# FlowController.net
KiCad netlist of a schematic drawn in EAGLE
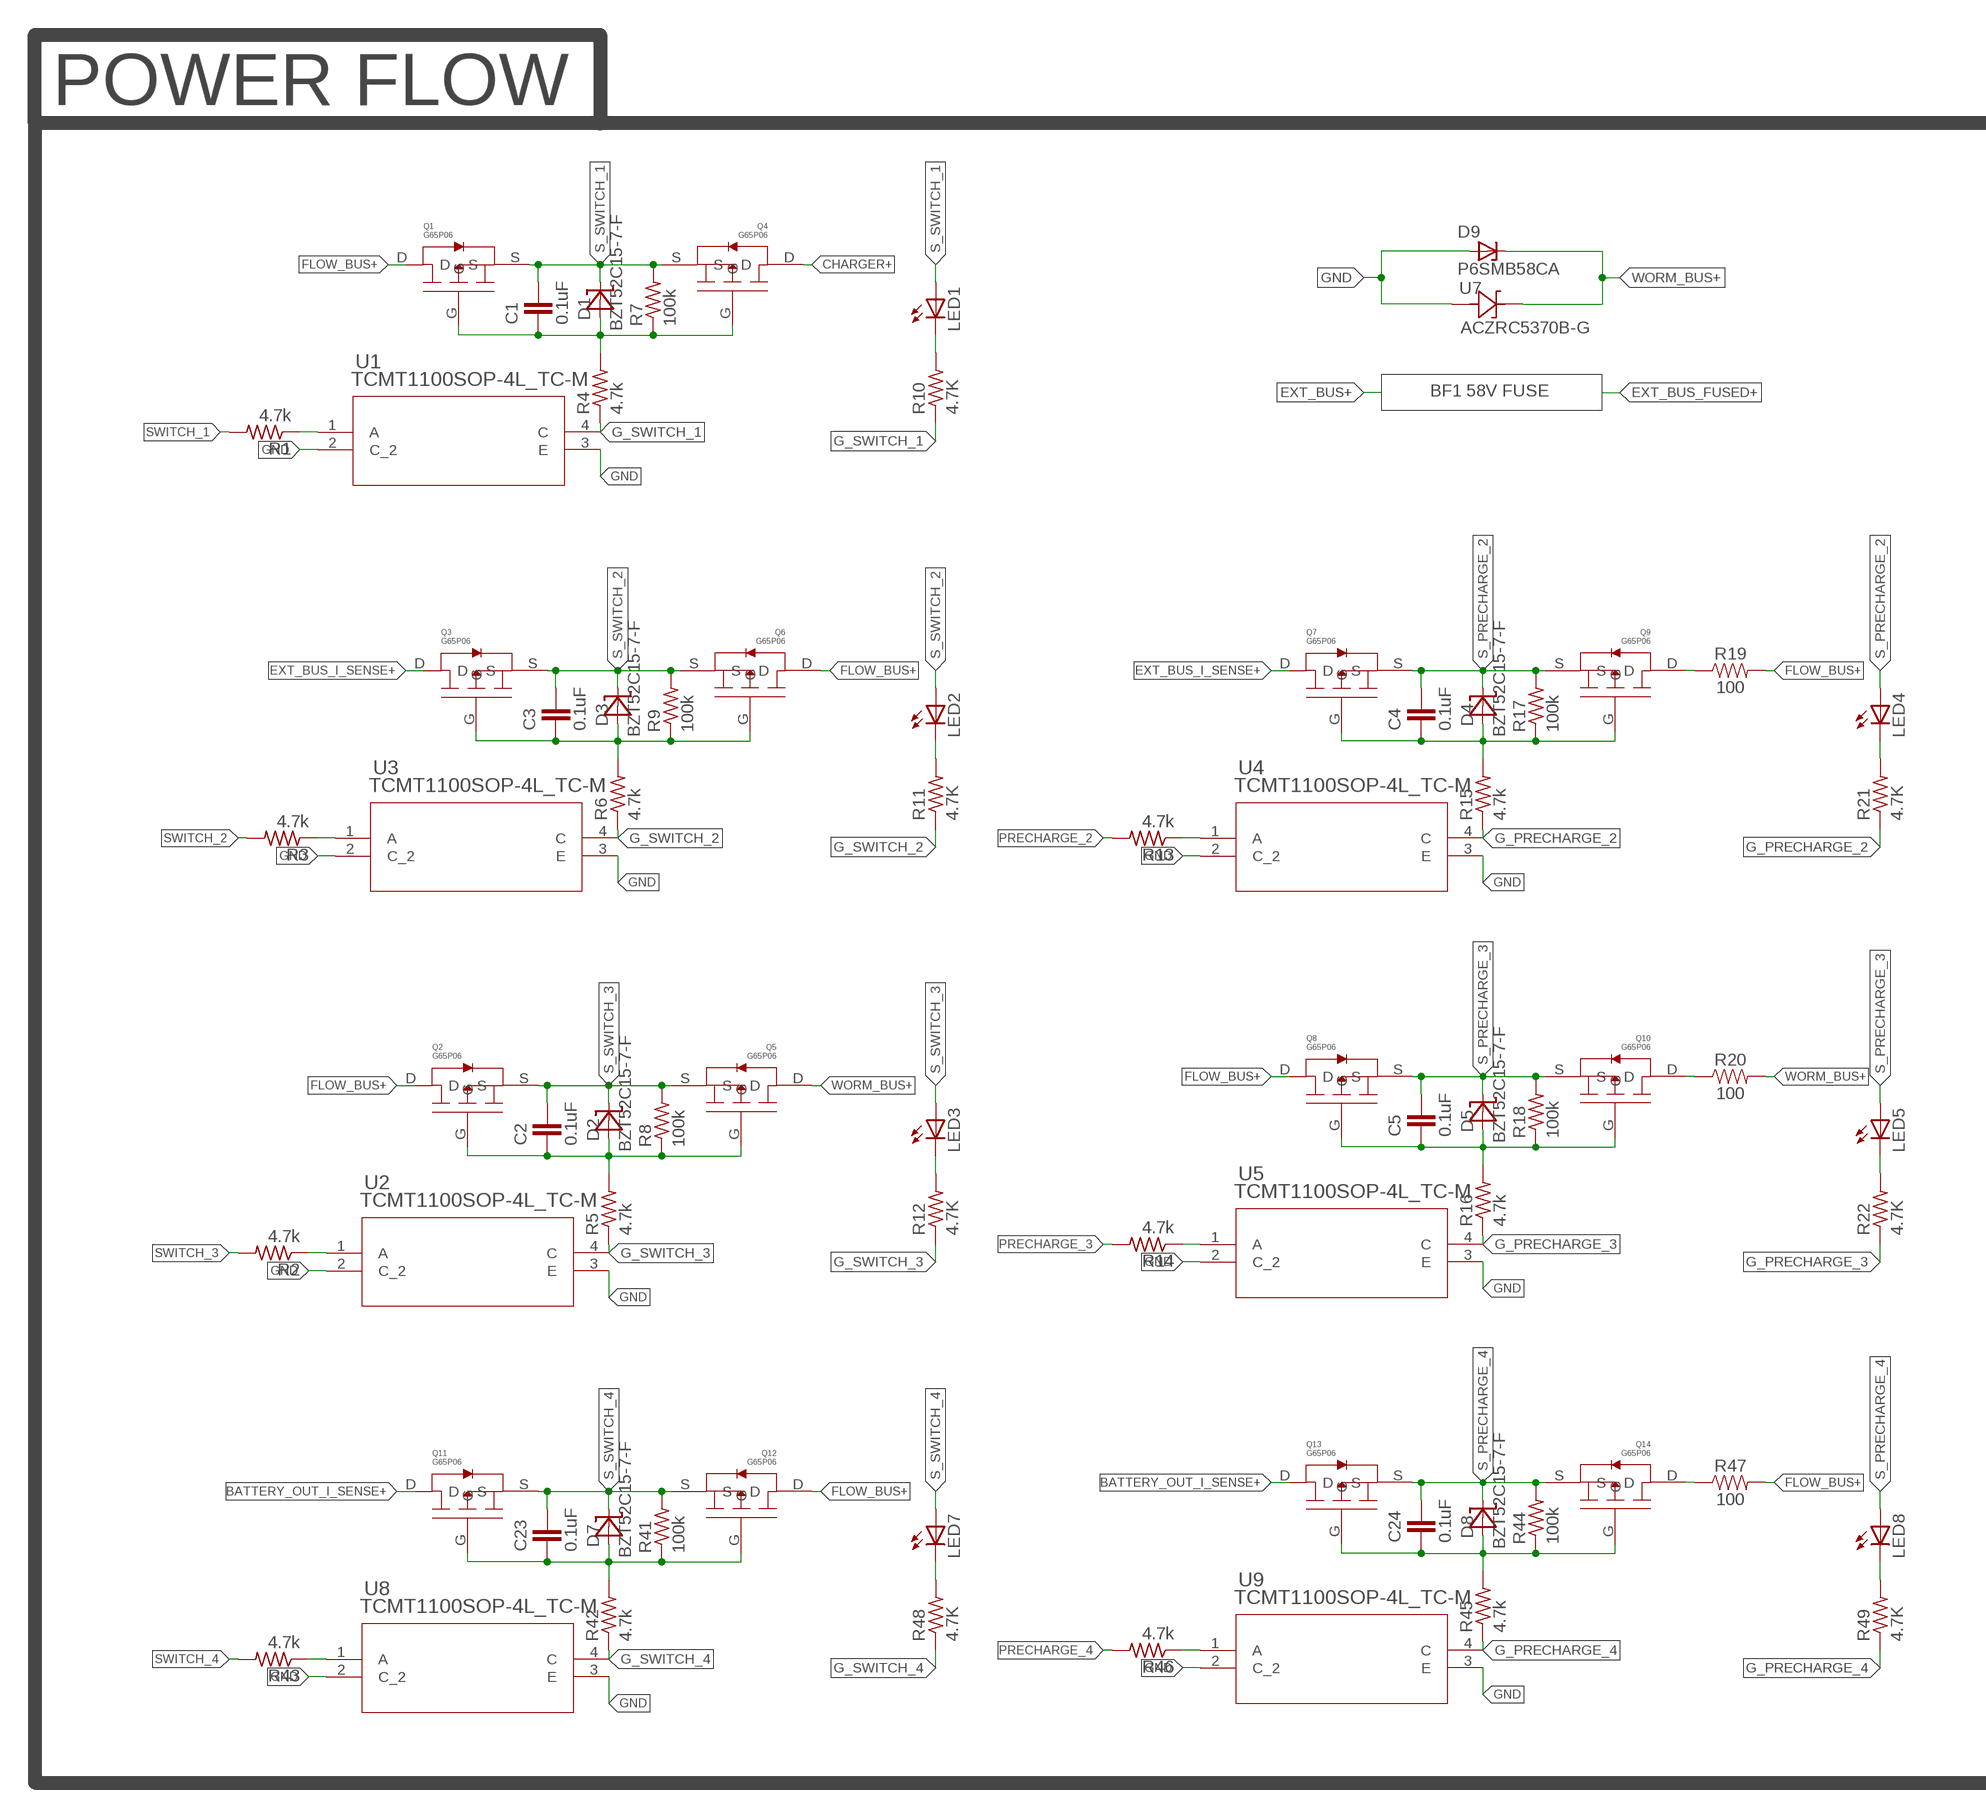
[diagram p0: schematic, sheet 1, part 1 of 2]
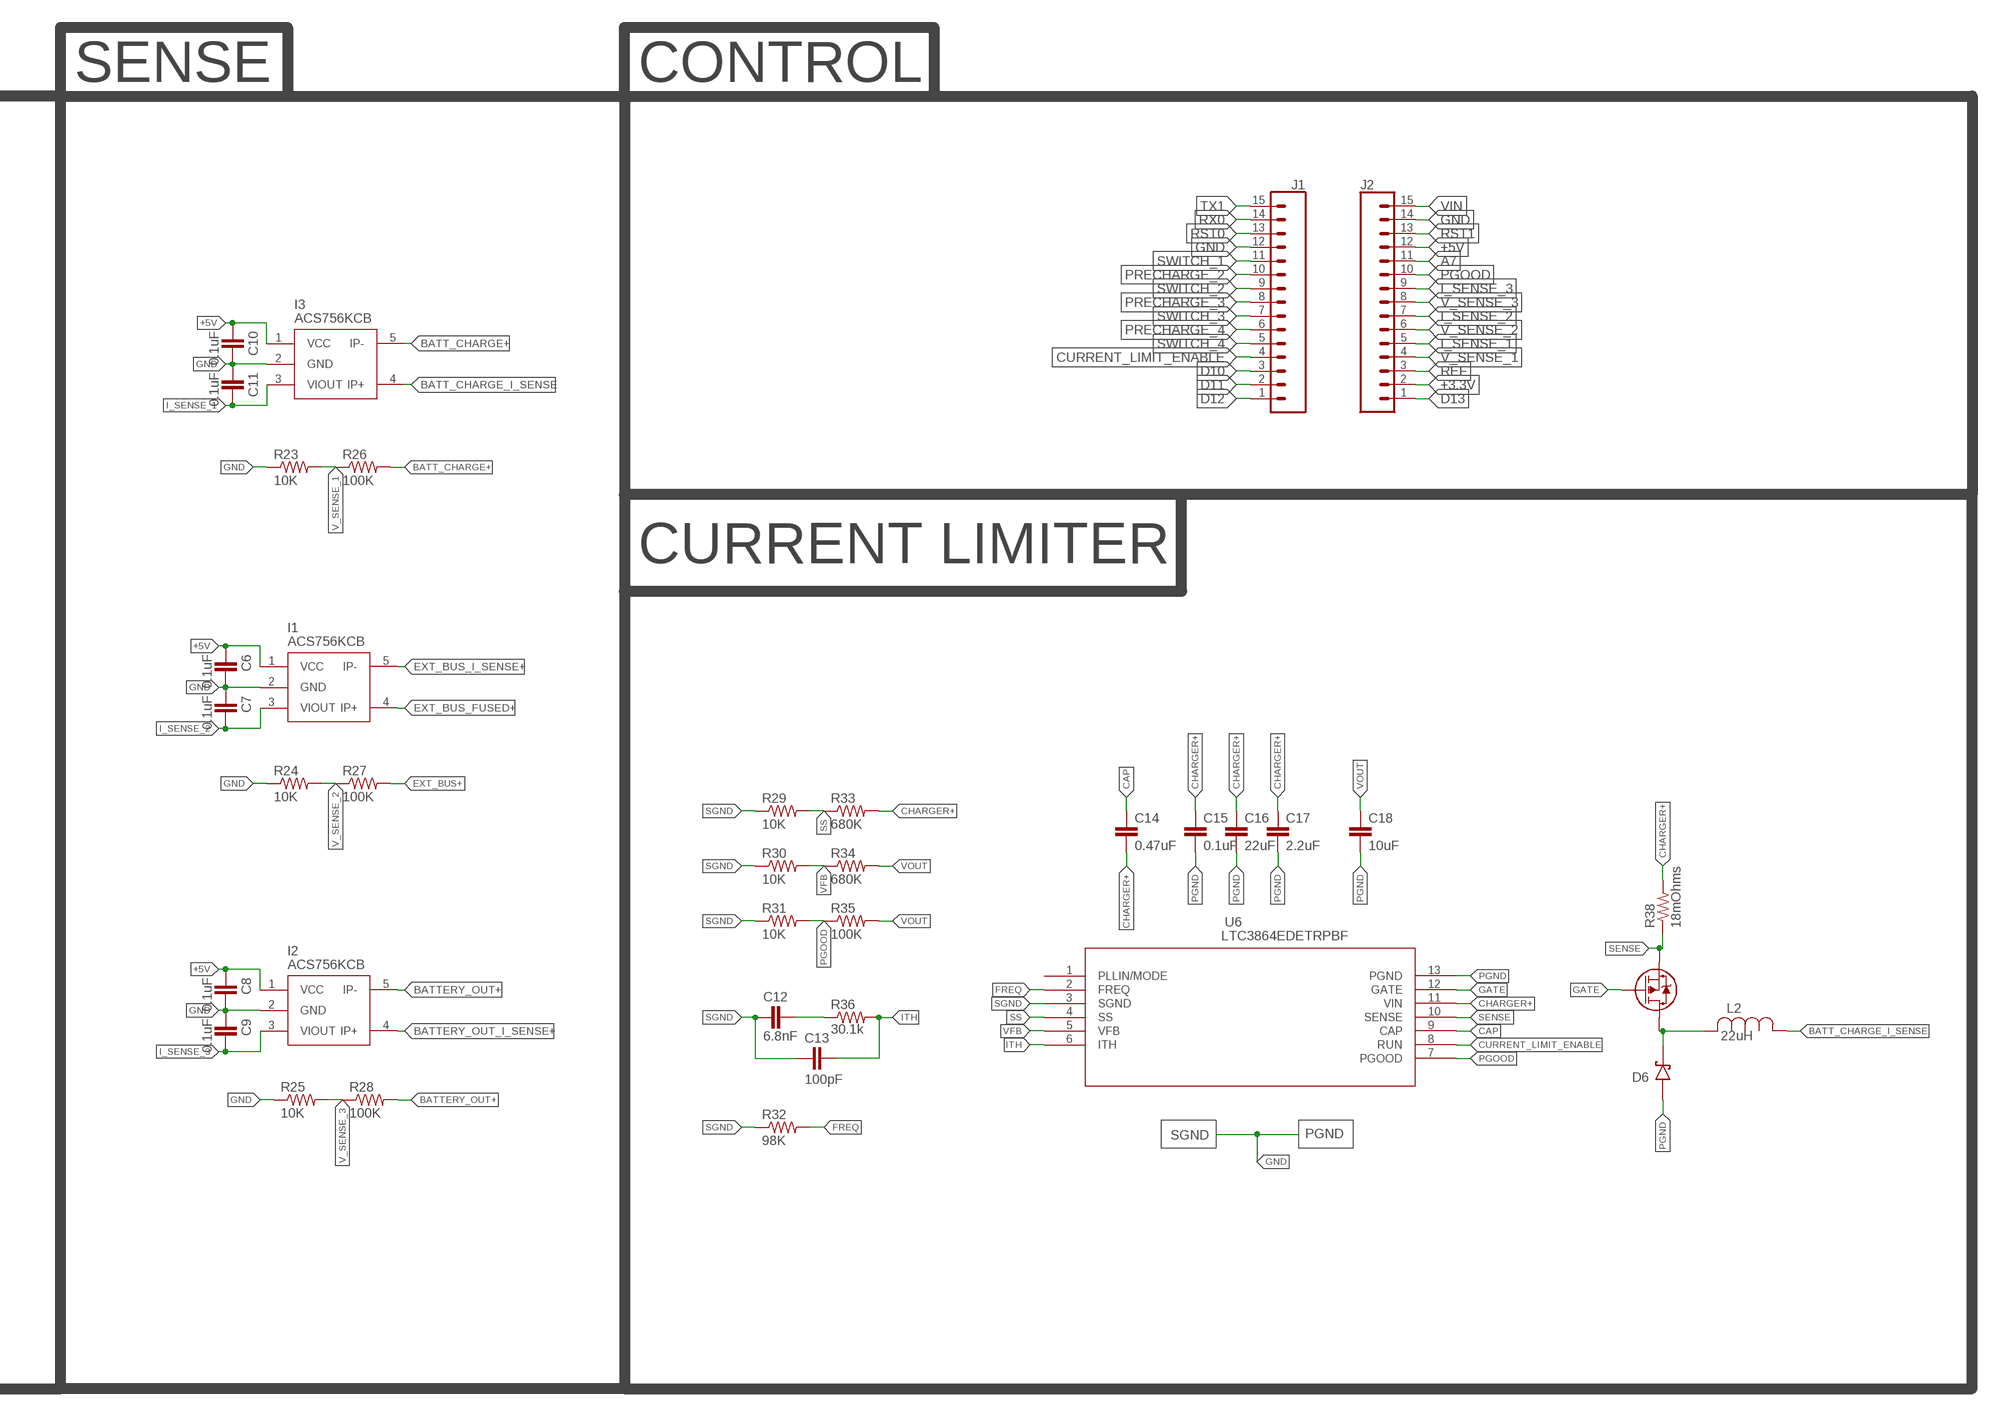
[diagram p1: schematic, sheet 1, part 2 of 2]

(export (version "E")
  (design (tool "Eeschema 10.0.6"))
  (components
    (comp (ref "C1")
      (value "0.1uF")
      (footprint "eagle-import:0805")
      (libsource (lib "eagle-import") (part "2.2UF-0805-25V-(+80/-20%)"))
    )
    (comp (ref "C2")
      (value "0.1uF")
      (footprint "eagle-import:0805")
      (libsource (lib "eagle-import") (part "2.2UF-0805-25V-(+80/-20%)"))
    )
    (comp (ref "C3")
      (value "0.1uF")
      (footprint "eagle-import:0805")
      (libsource (lib "eagle-import") (part "2.2UF-0805-25V-(+80/-20%)"))
    )
    (comp (ref "C4")
      (value "0.1uF")
      (footprint "eagle-import:0805")
      (libsource (lib "eagle-import") (part "2.2UF-0805-25V-(+80/-20%)"))
    )
    (comp (ref "C5")
      (value "0.1uF")
      (footprint "eagle-import:0805")
      (libsource (lib "eagle-import") (part "2.2UF-0805-25V-(+80/-20%)"))
    )
    (comp (ref "C6")
      (value "0.1uF")
      (footprint "eagle-import:0805")
      (libsource (lib "eagle-import") (part "2.2UF-0805-25V-(+80/-20%)"))
    )
    (comp (ref "C7")
      (value "0.1uF")
      (footprint "eagle-import:0805")
      (libsource (lib "eagle-import") (part "2.2UF-0805-25V-(+80/-20%)"))
    )
    (comp (ref "C8")
      (value "0.1uF")
      (footprint "eagle-import:0805")
      (libsource (lib "eagle-import") (part "2.2UF-0805-25V-(+80/-20%)"))
    )
    (comp (ref "C9")
      (value "0.1uF")
      (footprint "eagle-import:0805")
      (libsource (lib "eagle-import") (part "2.2UF-0805-25V-(+80/-20%)"))
    )
    (comp (ref "C10")
      (value "0.1uF")
      (footprint "eagle-import:0805")
      (libsource (lib "eagle-import") (part "2.2UF-0805-25V-(+80/-20%)"))
    )
    (comp (ref "C11")
      (value "0.1uF")
      (footprint "eagle-import:0805")
      (libsource (lib "eagle-import") (part "2.2UF-0805-25V-(+80/-20%)"))
    )
    (comp (ref "C12")
      (value "6.8nF")
      (footprint "eagle-import:0805")
      (libsource (lib "eagle-import") (part "2.2UF-0805-25V-(+80/-20%)"))
    )
    (comp (ref "C13")
      (value "100pF")
      (footprint "eagle-import:0805")
      (libsource (lib "eagle-import") (part "2.2UF-0805-25V-(+80/-20%)"))
    )
    (comp (ref "C14")
      (value "0.47uF")
      (footprint "eagle-import:0805")
      (libsource (lib "eagle-import") (part "2.2UF-0805-25V-(+80/-20%)"))
    )
    (comp (ref "C15")
      (value "0.1uF")
      (footprint "eagle-import:0805")
      (libsource (lib "eagle-import") (part "2.2UF-0805-25V-(+80/-20%)"))
    )
    (comp (ref "C16")
      (value "22uF")
      (footprint "eagle-import:1210")
      (libsource (lib "eagle-import") (part "10UF-1210-50V-20%"))
    )
    (comp (ref "C17")
      (value "2.2uF")
      (footprint "eagle-import:1210")
      (libsource (lib "eagle-import") (part "10UF-1210-50V-20%"))
    )
    (comp (ref "C18")
      (value "10uF")
      (footprint "eagle-import:1210")
      (libsource (lib "eagle-import") (part "10UF-1210-50V-20%"))
    )
    (comp (ref "C23")
      (value "0.1uF")
      (footprint "eagle-import:0805")
      (libsource (lib "eagle-import") (part "2.2UF-0805-25V-(+80/-20%)"))
    )
    (comp (ref "C24")
      (value "0.1uF")
      (footprint "eagle-import:0805")
      (libsource (lib "eagle-import") (part "2.2UF-0805-25V-(+80/-20%)"))
    )
    (comp (ref "D1")
      (value "BZT52C15-7-F")
      (footprint "eagle-import:SOD123")
      (fields (field (name "DIGI-KEY_PART_NUMBER") "BZT52C15-FDITR-ND") (field (name "MF") "Diodes Inc."))
      (libsource (lib "eagle-import") (part "BZT52C15-7-F"))
    )
    (comp (ref "D2")
      (value "BZT52C15-7-F")
      (footprint "eagle-import:SOD123")
      (fields (field (name "DIGI-KEY_PART_NUMBER") "BZT52C15-FDITR-ND") (field (name "MF") "Diodes Inc."))
      (libsource (lib "eagle-import") (part "BZT52C15-7-F"))
    )
    (comp (ref "D3")
      (value "BZT52C15-7-F")
      (footprint "eagle-import:SOD123")
      (fields (field (name "DIGI-KEY_PART_NUMBER") "BZT52C15-FDITR-ND") (field (name "MF") "Diodes Inc."))
      (libsource (lib "eagle-import") (part "BZT52C15-7-F"))
    )
    (comp (ref "D4")
      (value "BZT52C15-7-F")
      (footprint "eagle-import:SOD123")
      (fields (field (name "DIGI-KEY_PART_NUMBER") "BZT52C15-FDITR-ND") (field (name "MF") "Diodes Inc."))
      (libsource (lib "eagle-import") (part "BZT52C15-7-F"))
    )
    (comp (ref "D5")
      (value "BZT52C15-7-F")
      (footprint "eagle-import:SOD123")
      (fields (field (name "DIGI-KEY_PART_NUMBER") "BZT52C15-FDITR-ND") (field (name "MF") "Diodes Inc."))
      (libsource (lib "eagle-import") (part "BZT52C15-7-F"))
    )
    (comp (ref "D6")
      (value "MBR1560STR")
      (footprint "eagle-import:DIO_MBR1560STR")
      (fields (field (name "MF") "SMC Diode Solutions"))
      (libsource (lib "eagle-import") (part "MBR1560STR"))
    )
    (comp (ref "D7")
      (value "BZT52C15-7-F")
      (footprint "eagle-import:SOD123")
      (fields (field (name "DIGI-KEY_PART_NUMBER") "BZT52C15-FDITR-ND") (field (name "MF") "Diodes Inc."))
      (libsource (lib "eagle-import") (part "BZT52C15-7-F"))
    )
    (comp (ref "D8")
      (value "BZT52C15-7-F")
      (footprint "eagle-import:SOD123")
      (fields (field (name "DIGI-KEY_PART_NUMBER") "BZT52C15-FDITR-ND") (field (name "MF") "Diodes Inc."))
      (libsource (lib "eagle-import") (part "BZT52C15-7-F"))
    )
    (comp (ref "D9")
      (value "P6SMB58CA")
      (footprint "eagle-import:DO214AA")
      (fields (field (name "MF") "ON Semiconductor") (field (name "MPN") "1SMB5913BT3G"))
      (libsource (lib "eagle-import") (part "1SMB59BT3G13"))
    )
    (comp (ref "I1")
      (value "ACS756KCB")
      (footprint "eagle-import:ACS756KCB")
      (libsource (lib "eagle-import") (part "ACS756KCB"))
    )
    (comp (ref "I2")
      (value "ACS756KCB")
      (footprint "eagle-import:ACS756KCB")
      (libsource (lib "eagle-import") (part "ACS756KCB"))
    )
    (comp (ref "I3")
      (value "ACS756KCB")
      (footprint "eagle-import:ACS756KCB")
      (libsource (lib "eagle-import") (part "ACS756KCB"))
    )
    (comp (ref "J1")
      (value "CONN_15")
      (footprint "eagle-import:1X15")
      (libsource (lib "eagle-import") (part "CONN_15"))
    )
    (comp (ref "J2")
      (value "CONN_15")
      (footprint "eagle-import:1X15")
      (fields (field (name "SPICEPREFIX") "X"))
      (libsource (lib "eagle-import") (part "CONN_15"))
    )
    (comp (ref "L2")
      (value "22uH")
      (footprint "eagle-import:IND_IHLP-4040DZ_VIS")
      (fields
        (field (name "MANUFACTURER_PART_NUMBER") "IHLP4040DZER6R8M01")
        (field (name "COPYRIGHT") "Copyright (C) 2022 Ultra Librarian. All rights reserved.")
      )
      (libsource (lib "eagle-import") (part "IHLP4040DZER6R8M01"))
    )
    (comp (ref "LED1")
      (value "LEDCHIPLED_0805")
      (footprint "eagle-import:CHIPLED_0805")
      (libsource (lib "eagle-import") (part "LEDCHIPLED_0805"))
    )
    (comp (ref "LED2")
      (value "LEDCHIPLED_0805")
      (footprint "eagle-import:CHIPLED_0805")
      (libsource (lib "eagle-import") (part "LEDCHIPLED_0805"))
    )
    (comp (ref "LED3")
      (value "LEDCHIPLED_0805")
      (footprint "eagle-import:CHIPLED_0805")
      (libsource (lib "eagle-import") (part "LEDCHIPLED_0805"))
    )
    (comp (ref "LED4")
      (value "LEDCHIPLED_0805")
      (footprint "eagle-import:CHIPLED_0805")
      (libsource (lib "eagle-import") (part "LEDCHIPLED_0805"))
    )
    (comp (ref "LED5")
      (value "LEDCHIPLED_0805")
      (footprint "eagle-import:CHIPLED_0805")
      (libsource (lib "eagle-import") (part "LEDCHIPLED_0805"))
    )
    (comp (ref "LED7")
      (value "LEDCHIPLED_0805")
      (footprint "eagle-import:CHIPLED_0805")
      (libsource (lib "eagle-import") (part "LEDCHIPLED_0805"))
    )
    (comp (ref "LED8")
      (value "LEDCHIPLED_0805")
      (footprint "eagle-import:CHIPLED_0805")
      (libsource (lib "eagle-import") (part "LEDCHIPLED_0805"))
    )
    (comp (ref "Q1")
      (value "G65P06")
      (footprint "eagle-import:G65P06")
      (libsource (lib "eagle-import") (part "G65P06"))
    )
    (comp (ref "Q2")
      (value "G65P06")
      (footprint "eagle-import:G65P06")
      (libsource (lib "eagle-import") (part "G65P06"))
    )
    (comp (ref "Q3")
      (value "G65P06")
      (footprint "eagle-import:G65P06")
      (libsource (lib "eagle-import") (part "G65P06"))
    )
    (comp (ref "Q4")
      (value "G65P06")
      (footprint "eagle-import:G65P06")
      (libsource (lib "eagle-import") (part "G65P06"))
    )
    (comp (ref "Q5")
      (value "G65P06")
      (footprint "eagle-import:G65P06")
      (libsource (lib "eagle-import") (part "G65P06"))
    )
    (comp (ref "Q6")
      (value "G65P06")
      (footprint "eagle-import:G65P06")
      (libsource (lib "eagle-import") (part "G65P06"))
    )
    (comp (ref "Q7")
      (value "G65P06")
      (footprint "eagle-import:G65P06")
      (libsource (lib "eagle-import") (part "G65P06"))
    )
    (comp (ref "Q8")
      (value "G65P06")
      (footprint "eagle-import:G65P06")
      (libsource (lib "eagle-import") (part "G65P06"))
    )
    (comp (ref "Q9")
      (value "G65P06")
      (footprint "eagle-import:G65P06")
      (libsource (lib "eagle-import") (part "G65P06"))
    )
    (comp (ref "Q10")
      (value "G65P06")
      (footprint "eagle-import:G65P06")
      (libsource (lib "eagle-import") (part "G65P06"))
    )
    (comp (ref "Q11")
      (value "G65P06")
      (footprint "eagle-import:G65P06")
      (libsource (lib "eagle-import") (part "G65P06"))
    )
    (comp (ref "Q12")
      (value "G65P06")
      (footprint "eagle-import:G65P06")
      (libsource (lib "eagle-import") (part "G65P06"))
    )
    (comp (ref "Q13")
      (value "G65P06")
      (footprint "eagle-import:G65P06")
      (libsource (lib "eagle-import") (part "G65P06"))
    )
    (comp (ref "Q14")
      (value "G65P06")
      (footprint "eagle-import:G65P06")
      (libsource (lib "eagle-import") (part "G65P06"))
    )
    (comp (ref "R1")
      (value "4.7k")
      (footprint "eagle-import:M0805")
      (libsource (lib "eagle-import") (part "R-US_M0805"))
    )
    (comp (ref "R2")
      (value "4.7k")
      (footprint "eagle-import:M0805")
      (libsource (lib "eagle-import") (part "R-US_M0805"))
    )
    (comp (ref "R3")
      (value "4.7k")
      (footprint "eagle-import:M0805")
      (libsource (lib "eagle-import") (part "R-US_M0805"))
    )
    (comp (ref "R4")
      (value "4.7k")
      (footprint "eagle-import:M0805")
      (libsource (lib "eagle-import") (part "R-US_M0805"))
    )
    (comp (ref "R5")
      (value "4.7k")
      (footprint "eagle-import:M0805")
      (libsource (lib "eagle-import") (part "R-US_M0805"))
    )
    (comp (ref "R6")
      (value "4.7k")
      (footprint "eagle-import:M0805")
      (libsource (lib "eagle-import") (part "R-US_M0805"))
    )
    (comp (ref "R7")
      (value "100k")
      (footprint "eagle-import:M0805")
      (libsource (lib "eagle-import") (part "R-US_M0805"))
    )
    (comp (ref "R8")
      (value "100k")
      (footprint "eagle-import:M0805")
      (libsource (lib "eagle-import") (part "R-US_M0805"))
    )
    (comp (ref "R9")
      (value "100k")
      (footprint "eagle-import:M0805")
      (libsource (lib "eagle-import") (part "R-US_M0805"))
    )
    (comp (ref "R10")
      (value "4.7K")
      (footprint "eagle-import:M0805")
      (libsource (lib "eagle-import") (part "R-US_M0805"))
    )
    (comp (ref "R11")
      (value "4.7K")
      (footprint "eagle-import:M0805")
      (libsource (lib "eagle-import") (part "R-US_M0805"))
    )
    (comp (ref "R12")
      (value "4.7K")
      (footprint "eagle-import:M0805")
      (libsource (lib "eagle-import") (part "R-US_M0805"))
    )
    (comp (ref "R13")
      (value "4.7k")
      (footprint "eagle-import:M0805")
      (libsource (lib "eagle-import") (part "R-US_M0805"))
    )
    (comp (ref "R14")
      (value "4.7k")
      (footprint "eagle-import:M0805")
      (libsource (lib "eagle-import") (part "R-US_M0805"))
    )
    (comp (ref "R15")
      (value "4.7k")
      (footprint "eagle-import:M0805")
      (libsource (lib "eagle-import") (part "R-US_M0805"))
    )
    (comp (ref "R16")
      (value "4.7k")
      (footprint "eagle-import:M0805")
      (libsource (lib "eagle-import") (part "R-US_M0805"))
    )
    (comp (ref "R17")
      (value "100k")
      (footprint "eagle-import:M0805")
      (libsource (lib "eagle-import") (part "R-US_M0805"))
    )
    (comp (ref "R18")
      (value "100k")
      (footprint "eagle-import:M0805")
      (libsource (lib "eagle-import") (part "R-US_M0805"))
    )
    (comp (ref "R19")
      (value "100")
      (footprint "eagle-import:2512")
      (libsource (lib "eagle-import") (part "0.05OHM-2512-3W-1%"))
    )
    (comp (ref "R20")
      (value "100")
      (footprint "eagle-import:2512")
      (libsource (lib "eagle-import") (part "0.05OHM-2512-3W-1%"))
    )
    (comp (ref "R21")
      (value "4.7K")
      (footprint "eagle-import:M0805")
      (libsource (lib "eagle-import") (part "R-US_M0805"))
    )
    (comp (ref "R22")
      (value "4.7K")
      (footprint "eagle-import:M0805")
      (libsource (lib "eagle-import") (part "R-US_M0805"))
    )
    (comp (ref "R23")
      (value "10K")
      (footprint "eagle-import:M0805")
      (libsource (lib "eagle-import") (part "R-US_M0805"))
    )
    (comp (ref "R24")
      (value "10K")
      (footprint "eagle-import:M0805")
      (libsource (lib "eagle-import") (part "R-US_M0805"))
    )
    (comp (ref "R25")
      (value "10K")
      (footprint "eagle-import:M0805")
      (libsource (lib "eagle-import") (part "R-US_M0805"))
    )
    (comp (ref "R26")
      (value "100K")
      (footprint "eagle-import:M0805")
      (libsource (lib "eagle-import") (part "R-US_M0805"))
    )
    (comp (ref "R27")
      (value "100K")
      (footprint "eagle-import:M0805")
      (libsource (lib "eagle-import") (part "R-US_M0805"))
    )
    (comp (ref "R28")
      (value "100K")
      (footprint "eagle-import:M0805")
      (libsource (lib "eagle-import") (part "R-US_M0805"))
    )
    (comp (ref "R29")
      (value "10K")
      (footprint "eagle-import:M0805")
      (libsource (lib "eagle-import") (part "R-US_M0805"))
    )
    (comp (ref "R30")
      (value "10K")
      (footprint "eagle-import:M0805")
      (libsource (lib "eagle-import") (part "R-US_M0805"))
    )
    (comp (ref "R31")
      (value "10K")
      (footprint "eagle-import:M0805")
      (libsource (lib "eagle-import") (part "R-US_M0805"))
    )
    (comp (ref "R32")
      (value "98K")
      (footprint "eagle-import:M0805")
      (libsource (lib "eagle-import") (part "R-US_M0805"))
    )
    (comp (ref "R33")
      (value "680K")
      (footprint "eagle-import:M0805")
      (libsource (lib "eagle-import") (part "R-US_M0805"))
    )
    (comp (ref "R34")
      (value "680K")
      (footprint "eagle-import:M0805")
      (libsource (lib "eagle-import") (part "R-US_M0805"))
    )
    (comp (ref "R35")
      (value "100K")
      (footprint "eagle-import:M0805")
      (libsource (lib "eagle-import") (part "R-US_M0805"))
    )
    (comp (ref "R36")
      (value "30.1k")
      (footprint "eagle-import:M0805")
      (libsource (lib "eagle-import") (part "R-US_M0805"))
    )
    (comp (ref "R37")
      (value "RSJ250P10TL")
      (footprint "eagle-import:TRANS_R5009FNJ_ROM")
      (fields (field (name "COPYRIGHT") "Copyright (C) 2022 Ultra Librarian. All rights reserved."))
      (libsource (lib "eagle-import") (part "RSJ250P10TL"))
    )
    (comp (ref "R38")
      (value "18mOhms")
      (footprint "eagle-import:M0805")
      (libsource (lib "eagle-import") (part "R-US_M0805"))
    )
    (comp (ref "R41")
      (value "100k")
      (footprint "eagle-import:M0805")
      (libsource (lib "eagle-import") (part "R-US_M0805"))
    )
    (comp (ref "R42")
      (value "4.7k")
      (footprint "eagle-import:M0805")
      (libsource (lib "eagle-import") (part "R-US_M0805"))
    )
    (comp (ref "R43")
      (value "4.7k")
      (footprint "eagle-import:M0805")
      (libsource (lib "eagle-import") (part "R-US_M0805"))
    )
    (comp (ref "R44")
      (value "100k")
      (footprint "eagle-import:M0805")
      (libsource (lib "eagle-import") (part "R-US_M0805"))
    )
    (comp (ref "R45")
      (value "4.7k")
      (footprint "eagle-import:M0805")
      (libsource (lib "eagle-import") (part "R-US_M0805"))
    )
    (comp (ref "R46")
      (value "4.7k")
      (footprint "eagle-import:M0805")
      (libsource (lib "eagle-import") (part "R-US_M0805"))
    )
    (comp (ref "R47")
      (value "100")
      (footprint "eagle-import:2512")
      (libsource (lib "eagle-import") (part "0.05OHM-2512-3W-1%"))
    )
    (comp (ref "R48")
      (value "4.7K")
      (footprint "eagle-import:M0805")
      (libsource (lib "eagle-import") (part "R-US_M0805"))
    )
    (comp (ref "R49")
      (value "4.7K")
      (footprint "eagle-import:M0805")
      (libsource (lib "eagle-import") (part "R-US_M0805"))
    )
    (comp (ref "U1")
      (value "TCMT1100SOP-4L_TC-M")
      (footprint "eagle-import:SOP-4L_TC-M")
      (fields
        (field (name "MANUFACTURER_PART_NUMBER") "TCMT1100")
        (field (name "COPYRIGHT") "Copyright (C) 2022 Ultra Librarian. All rights reserved.")
      )
      (libsource (lib "eagle-import") (part "TCMT1100SOP-4L_TC-M"))
    )
    (comp (ref "U2")
      (value "TCMT1100SOP-4L_TC-M")
      (footprint "eagle-import:SOP-4L_TC-M")
      (fields
        (field (name "MANUFACTURER_PART_NUMBER") "TCMT1100")
        (field (name "COPYRIGHT") "Copyright (C) 2022 Ultra Librarian. All rights reserved.")
      )
      (libsource (lib "eagle-import") (part "TCMT1100SOP-4L_TC-M"))
    )
    (comp (ref "U3")
      (value "TCMT1100SOP-4L_TC-M")
      (footprint "eagle-import:SOP-4L_TC-M")
      (fields
        (field (name "MANUFACTURER_PART_NUMBER") "TCMT1100")
        (field (name "COPYRIGHT") "Copyright (C) 2022 Ultra Librarian. All rights reserved.")
      )
      (libsource (lib "eagle-import") (part "TCMT1100SOP-4L_TC-M"))
    )
    (comp (ref "U4")
      (value "TCMT1100SOP-4L_TC-M")
      (footprint "eagle-import:SOP-4L_TC-M")
      (fields
        (field (name "MANUFACTURER_PART_NUMBER") "TCMT1100")
        (field (name "COPYRIGHT") "Copyright (C) 2022 Ultra Librarian. All rights reserved.")
      )
      (libsource (lib "eagle-import") (part "TCMT1100SOP-4L_TC-M"))
    )
    (comp (ref "U5")
      (value "TCMT1100SOP-4L_TC-M")
      (footprint "eagle-import:SOP-4L_TC-M")
      (fields
        (field (name "MANUFACTURER_PART_NUMBER") "TCMT1100")
        (field (name "COPYRIGHT") "Copyright (C) 2022 Ultra Librarian. All rights reserved.")
      )
      (libsource (lib "eagle-import") (part "TCMT1100SOP-4L_TC-M"))
    )
    (comp (ref "U6")
      (value "LTC3864EDETRPBF")
      (footprint "eagle-import:DFN-12_DE")
      (fields
        (field (name "DIGI-KEY_PART_NUMBER") "161-LTC3864EDE#TRPBFTR-ND")
        (field (name "MF") "Analog Devices")
        (field (name "MP") "LTC3864EDE#TRPBF")
      )
      (libsource (lib "eagle-import") (part "LTC3864EDETRPBF"))
    )
    (comp (ref "U7")
      (value "ACZRC5370B-G")
      (footprint "eagle-import:ACZRC-G")
      (fields (field (name "COPYRIGHT") "Copyright (C) 2022 Ultra Librarian. All rights reserved."))
      (libsource (lib "eagle-import") (part "ACZRC5370B-G"))
    )
    (comp (ref "U8")
      (value "TCMT1100SOP-4L_TC-M")
      (footprint "eagle-import:SOP-4L_TC-M")
      (fields
        (field (name "MANUFACTURER_PART_NUMBER") "TCMT1100")
        (field (name "COPYRIGHT") "Copyright (C) 2022 Ultra Librarian. All rights reserved.")
      )
      (libsource (lib "eagle-import") (part "TCMT1100SOP-4L_TC-M"))
    )
    (comp (ref "U9")
      (value "TCMT1100SOP-4L_TC-M")
      (footprint "eagle-import:SOP-4L_TC-M")
      (fields
        (field (name "MANUFACTURER_PART_NUMBER") "TCMT1100")
        (field (name "COPYRIGHT") "Copyright (C) 2022 Ultra Librarian. All rights reserved.")
      )
      (libsource (lib "eagle-import") (part "TCMT1100SOP-4L_TC-M"))
    )
  )
  (nets
    (net (code "1") (name "+3.3V") (class "Default")
      (node (ref "J2") (pin "2") (pinfunction "2_2") (pintype "passive"))
    )
    (net (code "2") (name "+5V") (class "Default")
      (node (ref "C10") (pin "1") (pinfunction "1_1") (pintype "passive"))
      (node (ref "C6") (pin "1") (pinfunction "1_1") (pintype "passive"))
      (node (ref "C8") (pin "1") (pinfunction "1_1") (pintype "passive"))
      (node (ref "I1") (pin "1") (pinfunction "VCC_1") (pintype "bidirectional"))
      (node (ref "I2") (pin "1") (pinfunction "VCC_1") (pintype "bidirectional"))
      (node (ref "I3") (pin "1") (pinfunction "VCC_1") (pintype "bidirectional"))
      (node (ref "J2") (pin "12") (pinfunction "12_12") (pintype "passive"))
    )
    (net (code "3") (name "A7") (class "Default")
      (node (ref "J2") (pin "11") (pinfunction "11_11") (pintype "passive"))
    )
    (net (code "4") (name "BATTERY_OUT+") (class "Default")
      (node (ref "I2") (pin "5") (pinfunction "IP-_5") (pintype "bidirectional"))
      (node (ref "R28") (pin "2") (pinfunction "2_2") (pintype "passive"))
    )
    (net (code "5") (name "BATTERY_OUT_I_SENSE+") (class "Default")
      (node (ref "I2") (pin "4") (pinfunction "IP+_4") (pintype "bidirectional"))
      (node (ref "Q11") (pin "D") (pinfunction "D_D") (pintype "bidirectional"))
      (node (ref "Q13") (pin "D") (pinfunction "D_D") (pintype "bidirectional"))
    )
    (net (code "6") (name "BATT_CHARGE+") (class "Default")
      (node (ref "I3") (pin "5") (pinfunction "IP-_5") (pintype "bidirectional"))
      (node (ref "R26") (pin "2") (pinfunction "2_2") (pintype "passive"))
    )
    (net (code "7") (name "BATT_CHARGE_I_SENSE") (class "Default")
      (node (ref "I3") (pin "4") (pinfunction "IP+_4") (pintype "bidirectional"))
      (node (ref "L2") (pin "1") (pinfunction "1_1") (pintype "passive"))
    )
    (net (code "8") (name "CAP") (class "Default")
      (node (ref "C14") (pin "1") (pinfunction "1_1") (pintype "passive"))
      (node (ref "U6") (pin "9") (pinfunction "CAP_9") (pintype "passive"))
    )
    (net (code "9") (name "CHARGER+") (class "Default")
      (node (ref "C14") (pin "2") (pinfunction "2_2") (pintype "passive"))
      (node (ref "C15") (pin "1") (pinfunction "1_1") (pintype "passive"))
      (node (ref "C16") (pin "1") (pinfunction "1_1") (pintype "passive"))
      (node (ref "C17") (pin "1") (pinfunction "1_1") (pintype "passive"))
      (node (ref "Q4") (pin "D") (pinfunction "D_D") (pintype "bidirectional"))
      (node (ref "R33") (pin "2") (pinfunction "2_2") (pintype "passive"))
      (node (ref "R38") (pin "2") (pinfunction "2_2") (pintype "passive"))
      (node (ref "U6") (pin "11") (pinfunction "VIN_11") (pintype "input"))
    )
    (net (code "10") (name "CURRENT_LIMIT_ENABLE") (class "Default")
      (node (ref "J1") (pin "4") (pinfunction "4_4") (pintype "passive"))
      (node (ref "U6") (pin "8") (pinfunction "RUN_8") (pintype "input"))
    )
    (net (code "11") (name "D10") (class "Default")
      (node (ref "J1") (pin "3") (pinfunction "3_3") (pintype "passive"))
    )
    (net (code "12") (name "D11") (class "Default")
      (node (ref "J1") (pin "2") (pinfunction "2_2") (pintype "passive"))
    )
    (net (code "13") (name "D12") (class "Default")
      (node (ref "J1") (pin "1") (pinfunction "1_1") (pintype "passive"))
    )
    (net (code "14") (name "D13") (class "Default")
      (node (ref "J2") (pin "1") (pinfunction "1_1") (pintype "passive"))
    )
    (net (code "15") (name "EXT_BUS+") (class "Default")
      (node (ref "R27") (pin "2") (pinfunction "2_2") (pintype "passive"))
    )
    (net (code "16") (name "EXT_BUS_FUSED+") (class "Default")
      (node (ref "I1") (pin "4") (pinfunction "IP+_4") (pintype "bidirectional"))
    )
    (net (code "17") (name "EXT_BUS_I_SENSE+") (class "Default")
      (node (ref "I1") (pin "5") (pinfunction "IP-_5") (pintype "bidirectional"))
      (node (ref "Q3") (pin "D") (pinfunction "D_D") (pintype "bidirectional"))
      (node (ref "Q7") (pin "D") (pinfunction "D_D") (pintype "bidirectional"))
    )
    (net (code "18") (name "FLOW_BUS+") (class "Default")
      (node (ref "Q1") (pin "D") (pinfunction "D_D") (pintype "bidirectional"))
      (node (ref "Q12") (pin "D") (pinfunction "D_D") (pintype "bidirectional"))
      (node (ref "Q2") (pin "D") (pinfunction "D_D") (pintype "bidirectional"))
      (node (ref "Q6") (pin "D") (pinfunction "D_D") (pintype "bidirectional"))
      (node (ref "Q8") (pin "D") (pinfunction "D_D") (pintype "bidirectional"))
      (node (ref "R19") (pin "P$2") (pinfunction "2_P$2") (pintype "passive"))
      (node (ref "R47") (pin "P$2") (pinfunction "2_P$2") (pintype "passive"))
    )
    (net (code "19") (name "FREQ") (class "Default")
      (node (ref "R32") (pin "2") (pinfunction "2_2") (pintype "passive"))
      (node (ref "U6") (pin "2") (pinfunction "FREQ_2") (pintype "input"))
    )
    (net (code "20") (name "GATE") (class "Default")
      (node (ref "R37") (pin "1") (pinfunction "1_1") (pintype "passive"))
      (node (ref "U6") (pin "12") (pinfunction "GATE_12") (pintype "output"))
    )
    (net (code "21") (name "GND") (class "Default")
      (node (ref "C10") (pin "2") (pinfunction "2_2") (pintype "passive"))
      (node (ref "C11") (pin "1") (pinfunction "1_1") (pintype "passive"))
      (node (ref "C6") (pin "2") (pinfunction "2_2") (pintype "passive"))
      (node (ref "C7") (pin "1") (pinfunction "1_1") (pintype "passive"))
      (node (ref "C8") (pin "2") (pinfunction "2_2") (pintype "passive"))
      (node (ref "C9") (pin "1") (pinfunction "1_1") (pintype "passive"))
      (node (ref "D9") (pin "A") (pinfunction "A_A") (pintype "passive"))
      (node (ref "I1") (pin "2") (pinfunction "GND_2") (pintype "bidirectional"))
      (node (ref "I2") (pin "2") (pinfunction "GND_2") (pintype "bidirectional"))
      (node (ref "I3") (pin "2") (pinfunction "GND_2") (pintype "bidirectional"))
      (node (ref "J1") (pin "12") (pinfunction "12_12") (pintype "passive"))
      (node (ref "J2") (pin "14") (pinfunction "14_14") (pintype "passive"))
      (node (ref "R23") (pin "1") (pinfunction "1_1") (pintype "passive"))
      (node (ref "R24") (pin "1") (pinfunction "1_1") (pintype "passive"))
      (node (ref "R25") (pin "1") (pinfunction "1_1") (pintype "passive"))
      (node (ref "U1") (pin "2") (pinfunction "C_2_2") (pintype "passive"))
      (node (ref "U1") (pin "3") (pinfunction "E_3") (pintype "passive"))
      (node (ref "U2") (pin "2") (pinfunction "C_2_2") (pintype "passive"))
      (node (ref "U2") (pin "3") (pinfunction "E_3") (pintype "passive"))
      (node (ref "U3") (pin "2") (pinfunction "C_2_2") (pintype "passive"))
      (node (ref "U3") (pin "3") (pinfunction "E_3") (pintype "passive"))
      (node (ref "U4") (pin "2") (pinfunction "C_2_2") (pintype "passive"))
      (node (ref "U4") (pin "3") (pinfunction "E_3") (pintype "passive"))
      (node (ref "U5") (pin "2") (pinfunction "C_2_2") (pintype "passive"))
      (node (ref "U5") (pin "3") (pinfunction "E_3") (pintype "passive"))
      (node (ref "U7") (pin "2") (pinfunction "2_2") (pintype "passive"))
      (node (ref "U8") (pin "2") (pinfunction "C_2_2") (pintype "passive"))
      (node (ref "U8") (pin "3") (pinfunction "E_3") (pintype "passive"))
      (node (ref "U9") (pin "2") (pinfunction "C_2_2") (pintype "passive"))
      (node (ref "U9") (pin "3") (pinfunction "E_3") (pintype "passive"))
    )
    (net (code "22") (name "G_PRECHARGE_2") (class "Default")
      (node (ref "R15") (pin "1") (pinfunction "1_1") (pintype "passive"))
      (node (ref "R21") (pin "1") (pinfunction "1_1") (pintype "passive"))
      (node (ref "U4") (pin "4") (pinfunction "C_4") (pintype "passive"))
    )
    (net (code "23") (name "G_PRECHARGE_3") (class "Default")
      (node (ref "R16") (pin "1") (pinfunction "1_1") (pintype "passive"))
      (node (ref "R22") (pin "1") (pinfunction "1_1") (pintype "passive"))
      (node (ref "U5") (pin "4") (pinfunction "C_4") (pintype "passive"))
    )
    (net (code "24") (name "G_PRECHARGE_4") (class "Default")
      (node (ref "R45") (pin "1") (pinfunction "1_1") (pintype "passive"))
      (node (ref "R49") (pin "1") (pinfunction "1_1") (pintype "passive"))
      (node (ref "U9") (pin "4") (pinfunction "C_4") (pintype "passive"))
    )
    (net (code "25") (name "G_SWITCH_1") (class "Default")
      (node (ref "R10") (pin "1") (pinfunction "1_1") (pintype "passive"))
      (node (ref "R4") (pin "1") (pinfunction "1_1") (pintype "passive"))
      (node (ref "U1") (pin "4") (pinfunction "C_4") (pintype "passive"))
    )
    (net (code "26") (name "G_SWITCH_2") (class "Default")
      (node (ref "R11") (pin "1") (pinfunction "1_1") (pintype "passive"))
      (node (ref "R6") (pin "1") (pinfunction "1_1") (pintype "passive"))
      (node (ref "U3") (pin "4") (pinfunction "C_4") (pintype "passive"))
    )
    (net (code "27") (name "G_SWITCH_3") (class "Default")
      (node (ref "R12") (pin "1") (pinfunction "1_1") (pintype "passive"))
      (node (ref "R5") (pin "1") (pinfunction "1_1") (pintype "passive"))
      (node (ref "U2") (pin "4") (pinfunction "C_4") (pintype "passive"))
    )
    (net (code "28") (name "G_SWITCH_4") (class "Default")
      (node (ref "R42") (pin "1") (pinfunction "1_1") (pintype "passive"))
      (node (ref "R48") (pin "1") (pinfunction "1_1") (pintype "passive"))
      (node (ref "U8") (pin "4") (pinfunction "C_4") (pintype "passive"))
    )
    (net (code "29") (name "ITH") (class "Default")
      (node (ref "C13") (pin "2") (pinfunction "2_2") (pintype "passive"))
      (node (ref "R36") (pin "2") (pinfunction "2_2") (pintype "passive"))
      (node (ref "U6") (pin "6") (pinfunction "ITH_6") (pintype "output"))
    )
    (net (code "30") (name "I_SENSE_1") (class "Default")
      (node (ref "C11") (pin "2") (pinfunction "2_2") (pintype "passive"))
      (node (ref "I3") (pin "3") (pinfunction "VIOUT_3") (pintype "bidirectional"))
      (node (ref "J2") (pin "5") (pinfunction "5_5") (pintype "passive"))
    )
    (net (code "31") (name "I_SENSE_2") (class "Default")
      (node (ref "C7") (pin "2") (pinfunction "2_2") (pintype "passive"))
      (node (ref "I1") (pin "3") (pinfunction "VIOUT_3") (pintype "bidirectional"))
      (node (ref "J2") (pin "7") (pinfunction "7_7") (pintype "passive"))
    )
    (net (code "32") (name "I_SENSE_3") (class "Default")
      (node (ref "C9") (pin "2") (pinfunction "2_2") (pintype "passive"))
      (node (ref "I2") (pin "3") (pinfunction "VIOUT_3") (pintype "bidirectional"))
      (node (ref "J2") (pin "9") (pinfunction "9_9") (pintype "passive"))
    )
    (net (code "33") (name "Net-(C1-Pad1)") (class "Default")
      (node (ref "C1") (pin "1") (pinfunction "1_1") (pintype "passive"))
      (node (ref "D1") (pin "A") (pinfunction "A_A") (pintype "passive"))
      (node (ref "Q1") (pin "G") (pinfunction "G_G") (pintype "bidirectional"))
      (node (ref "Q4") (pin "G") (pinfunction "G_G") (pintype "bidirectional"))
      (node (ref "R4") (pin "2") (pinfunction "2_2") (pintype "passive"))
      (node (ref "R7") (pin "1") (pinfunction "1_1") (pintype "passive"))
    )
    (net (code "34") (name "Net-(C2-Pad1)") (class "Default")
      (node (ref "C2") (pin "1") (pinfunction "1_1") (pintype "passive"))
      (node (ref "D2") (pin "A") (pinfunction "A_A") (pintype "passive"))
      (node (ref "Q2") (pin "G") (pinfunction "G_G") (pintype "bidirectional"))
      (node (ref "Q5") (pin "G") (pinfunction "G_G") (pintype "bidirectional"))
      (node (ref "R5") (pin "2") (pinfunction "2_2") (pintype "passive"))
      (node (ref "R8") (pin "1") (pinfunction "1_1") (pintype "passive"))
    )
    (net (code "35") (name "Net-(C3-Pad1)") (class "Default")
      (node (ref "C3") (pin "1") (pinfunction "1_1") (pintype "passive"))
      (node (ref "D3") (pin "A") (pinfunction "A_A") (pintype "passive"))
      (node (ref "Q3") (pin "G") (pinfunction "G_G") (pintype "bidirectional"))
      (node (ref "Q6") (pin "G") (pinfunction "G_G") (pintype "bidirectional"))
      (node (ref "R6") (pin "2") (pinfunction "2_2") (pintype "passive"))
      (node (ref "R9") (pin "1") (pinfunction "1_1") (pintype "passive"))
    )
    (net (code "36") (name "Net-(C4-Pad1)") (class "Default")
      (node (ref "C4") (pin "1") (pinfunction "1_1") (pintype "passive"))
      (node (ref "D4") (pin "A") (pinfunction "A_A") (pintype "passive"))
      (node (ref "Q7") (pin "G") (pinfunction "G_G") (pintype "bidirectional"))
      (node (ref "Q9") (pin "G") (pinfunction "G_G") (pintype "bidirectional"))
      (node (ref "R15") (pin "2") (pinfunction "2_2") (pintype "passive"))
      (node (ref "R17") (pin "1") (pinfunction "1_1") (pintype "passive"))
    )
    (net (code "37") (name "Net-(C5-Pad1)") (class "Default")
      (node (ref "C5") (pin "1") (pinfunction "1_1") (pintype "passive"))
      (node (ref "D5") (pin "A") (pinfunction "A_A") (pintype "passive"))
      (node (ref "Q10") (pin "G") (pinfunction "G_G") (pintype "bidirectional"))
      (node (ref "Q8") (pin "G") (pinfunction "G_G") (pintype "bidirectional"))
      (node (ref "R16") (pin "2") (pinfunction "2_2") (pintype "passive"))
      (node (ref "R18") (pin "1") (pinfunction "1_1") (pintype "passive"))
    )
    (net (code "38") (name "Net-(C12-Pad2)") (class "Default")
      (node (ref "C12") (pin "2") (pinfunction "2_2") (pintype "passive"))
      (node (ref "R36") (pin "1") (pinfunction "1_1") (pintype "passive"))
    )
    (net (code "39") (name "Net-(C23-Pad1)") (class "Default")
      (node (ref "C23") (pin "1") (pinfunction "1_1") (pintype "passive"))
      (node (ref "D7") (pin "A") (pinfunction "A_A") (pintype "passive"))
      (node (ref "Q11") (pin "G") (pinfunction "G_G") (pintype "bidirectional"))
      (node (ref "Q12") (pin "G") (pinfunction "G_G") (pintype "bidirectional"))
      (node (ref "R41") (pin "1") (pinfunction "1_1") (pintype "passive"))
      (node (ref "R42") (pin "2") (pinfunction "2_2") (pintype "passive"))
    )
    (net (code "40") (name "Net-(C24-Pad1)") (class "Default")
      (node (ref "C24") (pin "1") (pinfunction "1_1") (pintype "passive"))
      (node (ref "D8") (pin "A") (pinfunction "A_A") (pintype "passive"))
      (node (ref "Q13") (pin "G") (pinfunction "G_G") (pintype "bidirectional"))
      (node (ref "Q14") (pin "G") (pinfunction "G_G") (pintype "bidirectional"))
      (node (ref "R44") (pin "1") (pinfunction "1_1") (pintype "passive"))
      (node (ref "R45") (pin "2") (pinfunction "2_2") (pintype "passive"))
    )
    (net (code "41") (name "Net-(LED1-PadC)") (class "Default")
      (node (ref "LED1") (pin "C") (pinfunction "C_C") (pintype "passive"))
      (node (ref "R10") (pin "2") (pinfunction "2_2") (pintype "passive"))
    )
    (net (code "42") (name "Net-(LED2-PadC)") (class "Default")
      (node (ref "LED2") (pin "C") (pinfunction "C_C") (pintype "passive"))
      (node (ref "R11") (pin "2") (pinfunction "2_2") (pintype "passive"))
    )
    (net (code "43") (name "Net-(LED3-PadC)") (class "Default")
      (node (ref "LED3") (pin "C") (pinfunction "C_C") (pintype "passive"))
      (node (ref "R12") (pin "2") (pinfunction "2_2") (pintype "passive"))
    )
    (net (code "44") (name "Net-(LED4-PadC)") (class "Default")
      (node (ref "LED4") (pin "C") (pinfunction "C_C") (pintype "passive"))
      (node (ref "R21") (pin "2") (pinfunction "2_2") (pintype "passive"))
    )
    (net (code "45") (name "Net-(LED5-PadC)") (class "Default")
      (node (ref "LED5") (pin "C") (pinfunction "C_C") (pintype "passive"))
      (node (ref "R22") (pin "2") (pinfunction "2_2") (pintype "passive"))
    )
    (net (code "46") (name "Net-(LED7-PadC)") (class "Default")
      (node (ref "LED7") (pin "C") (pinfunction "C_C") (pintype "passive"))
      (node (ref "R48") (pin "2") (pinfunction "2_2") (pintype "passive"))
    )
    (net (code "47") (name "Net-(LED8-PadC)") (class "Default")
      (node (ref "LED8") (pin "C") (pinfunction "C_C") (pintype "passive"))
      (node (ref "R49") (pin "2") (pinfunction "2_2") (pintype "passive"))
    )
    (net (code "48") (name "Net-(R19-1)") (class "Default")
      (node (ref "Q9") (pin "D") (pinfunction "D_D") (pintype "bidirectional"))
      (node (ref "R19") (pin "P$1") (pinfunction "1_P$1") (pintype "passive"))
    )
    (net (code "49") (name "Net-(R20-1)") (class "Default")
      (node (ref "Q10") (pin "D") (pinfunction "D_D") (pintype "bidirectional"))
      (node (ref "R20") (pin "P$1") (pinfunction "1_P$1") (pintype "passive"))
    )
    (net (code "50") (name "Net-(R37-3)") (class "Default")
      (node (ref "D6") (pin "3") (pinfunction "K_3") (pintype "passive"))
      (node (ref "D6") (pin "4") (pinfunction "K_4") (pintype "passive"))
      (node (ref "L2") (pin "2") (pinfunction "2_2") (pintype "passive"))
      (node (ref "R37") (pin "2") (pinfunction "3_2") (pintype "passive"))
    )
    (net (code "51") (name "Net-(R47-1)") (class "Default")
      (node (ref "Q14") (pin "D") (pinfunction "D_D") (pintype "bidirectional"))
      (node (ref "R47") (pin "P$1") (pinfunction "1_P$1") (pintype "passive"))
    )
    (net (code "52") (name "Net-(U1-A)") (class "Default")
      (node (ref "R1") (pin "1") (pinfunction "1_1") (pintype "passive"))
      (node (ref "U1") (pin "1") (pinfunction "A_1") (pintype "passive"))
    )
    (net (code "53") (name "Net-(U2-A)") (class "Default")
      (node (ref "R2") (pin "1") (pinfunction "1_1") (pintype "passive"))
      (node (ref "U2") (pin "1") (pinfunction "A_1") (pintype "passive"))
    )
    (net (code "54") (name "Net-(U3-A)") (class "Default")
      (node (ref "R3") (pin "1") (pinfunction "1_1") (pintype "passive"))
      (node (ref "U3") (pin "1") (pinfunction "A_1") (pintype "passive"))
    )
    (net (code "55") (name "Net-(U4-A)") (class "Default")
      (node (ref "R13") (pin "1") (pinfunction "1_1") (pintype "passive"))
      (node (ref "U4") (pin "1") (pinfunction "A_1") (pintype "passive"))
    )
    (net (code "56") (name "Net-(U5-A)") (class "Default")
      (node (ref "R14") (pin "1") (pinfunction "1_1") (pintype "passive"))
      (node (ref "U5") (pin "1") (pinfunction "A_1") (pintype "passive"))
    )
    (net (code "57") (name "Net-(U8-A)") (class "Default")
      (node (ref "R43") (pin "1") (pinfunction "1_1") (pintype "passive"))
      (node (ref "U8") (pin "1") (pinfunction "A_1") (pintype "passive"))
    )
    (net (code "58") (name "Net-(U9-A)") (class "Default")
      (node (ref "R46") (pin "1") (pinfunction "1_1") (pintype "passive"))
      (node (ref "U9") (pin "1") (pinfunction "A_1") (pintype "passive"))
    )
    (net (code "59") (name "PGND") (class "Default")
      (node (ref "C15") (pin "2") (pinfunction "2_2") (pintype "passive"))
      (node (ref "C16") (pin "2") (pinfunction "2_2") (pintype "passive"))
      (node (ref "C17") (pin "2") (pinfunction "2_2") (pintype "passive"))
      (node (ref "C18") (pin "2") (pinfunction "2_2") (pintype "passive"))
      (node (ref "D6") (pin "1") (pinfunction "A_1") (pintype "passive"))
      (node (ref "D6") (pin "2") (pinfunction "A_2") (pintype "passive"))
      (node (ref "U6") (pin "13") (pinfunction "PGND_13") (pintype "power_in"))
    )
    (net (code "60") (name "PGOOD") (class "Default")
      (node (ref "J2") (pin "10") (pinfunction "10_10") (pintype "passive"))
      (node (ref "R31") (pin "2") (pinfunction "2_2") (pintype "passive"))
      (node (ref "R35") (pin "1") (pinfunction "1_1") (pintype "passive"))
      (node (ref "U6") (pin "7") (pinfunction "PGOOD_7") (pintype "output"))
    )
    (net (code "61") (name "PRECHARGE_2") (class "Default")
      (node (ref "J1") (pin "10") (pinfunction "10_10") (pintype "passive"))
      (node (ref "R13") (pin "2") (pinfunction "2_2") (pintype "passive"))
    )
    (net (code "62") (name "PRECHARGE_3") (class "Default")
      (node (ref "J1") (pin "8") (pinfunction "8_8") (pintype "passive"))
      (node (ref "R14") (pin "2") (pinfunction "2_2") (pintype "passive"))
    )
    (net (code "63") (name "PRECHARGE_4") (class "Default")
      (node (ref "J1") (pin "6") (pinfunction "6_6") (pintype "passive"))
      (node (ref "R46") (pin "2") (pinfunction "2_2") (pintype "passive"))
    )
    (net (code "64") (name "REF") (class "Default")
      (node (ref "J2") (pin "3") (pinfunction "3_3") (pintype "passive"))
    )
    (net (code "65") (name "RST0") (class "Default")
      (node (ref "J1") (pin "13") (pinfunction "13_13") (pintype "passive"))
    )
    (net (code "66") (name "RST1") (class "Default")
      (node (ref "J2") (pin "13") (pinfunction "13_13") (pintype "passive"))
    )
    (net (code "67") (name "RX0") (class "Default")
      (node (ref "J1") (pin "14") (pinfunction "14_14") (pintype "passive"))
    )
    (net (code "68") (name "SENSE") (class "Default")
      (node (ref "R37") (pin "3") (pinfunction "2_3") (pintype "passive"))
      (node (ref "R38") (pin "1") (pinfunction "1_1") (pintype "passive"))
      (node (ref "U6") (pin "10") (pinfunction "SENSE_10") (pintype "input"))
    )
    (net (code "69") (name "SGND") (class "Default")
      (node (ref "C12") (pin "1") (pinfunction "1_1") (pintype "passive"))
      (node (ref "C13") (pin "1") (pinfunction "1_1") (pintype "passive"))
      (node (ref "R29") (pin "1") (pinfunction "1_1") (pintype "passive"))
      (node (ref "R30") (pin "1") (pinfunction "1_1") (pintype "passive"))
      (node (ref "R31") (pin "1") (pinfunction "1_1") (pintype "passive"))
      (node (ref "R32") (pin "1") (pinfunction "1_1") (pintype "passive"))
      (node (ref "U6") (pin "3") (pinfunction "SGND_3") (pintype "power_in"))
    )
    (net (code "70") (name "SS") (class "Default")
      (node (ref "R29") (pin "2") (pinfunction "2_2") (pintype "passive"))
      (node (ref "R33") (pin "1") (pinfunction "1_1") (pintype "passive"))
      (node (ref "U6") (pin "4") (pinfunction "SS_4") (pintype "input"))
    )
    (net (code "71") (name "SWITCH_1") (class "Default")
      (node (ref "J1") (pin "11") (pinfunction "11_11") (pintype "passive"))
      (node (ref "R1") (pin "2") (pinfunction "2_2") (pintype "passive"))
    )
    (net (code "72") (name "SWITCH_2") (class "Default")
      (node (ref "J1") (pin "9") (pinfunction "9_9") (pintype "passive"))
      (node (ref "R3") (pin "2") (pinfunction "2_2") (pintype "passive"))
    )
    (net (code "73") (name "SWITCH_3") (class "Default")
      (node (ref "J1") (pin "7") (pinfunction "7_7") (pintype "passive"))
      (node (ref "R2") (pin "2") (pinfunction "2_2") (pintype "passive"))
    )
    (net (code "74") (name "SWITCH_4") (class "Default")
      (node (ref "J1") (pin "5") (pinfunction "5_5") (pintype "passive"))
      (node (ref "R43") (pin "2") (pinfunction "2_2") (pintype "passive"))
    )
    (net (code "75") (name "S_PRECHARGE_2") (class "Default")
      (node (ref "C4") (pin "2") (pinfunction "2_2") (pintype "passive"))
      (node (ref "D4") (pin "C") (pinfunction "C_C") (pintype "passive"))
      (node (ref "LED4") (pin "A") (pinfunction "A_A") (pintype "passive"))
      (node (ref "Q7") (pin "S") (pinfunction "S_S") (pintype "bidirectional"))
      (node (ref "Q9") (pin "S") (pinfunction "S_S") (pintype "bidirectional"))
      (node (ref "R17") (pin "2") (pinfunction "2_2") (pintype "passive"))
    )
    (net (code "76") (name "S_PRECHARGE_3") (class "Default")
      (node (ref "C5") (pin "2") (pinfunction "2_2") (pintype "passive"))
      (node (ref "D5") (pin "C") (pinfunction "C_C") (pintype "passive"))
      (node (ref "LED5") (pin "A") (pinfunction "A_A") (pintype "passive"))
      (node (ref "Q10") (pin "S") (pinfunction "S_S") (pintype "bidirectional"))
      (node (ref "Q8") (pin "S") (pinfunction "S_S") (pintype "bidirectional"))
      (node (ref "R18") (pin "2") (pinfunction "2_2") (pintype "passive"))
    )
    (net (code "77") (name "S_PRECHARGE_4") (class "Default")
      (node (ref "C24") (pin "2") (pinfunction "2_2") (pintype "passive"))
      (node (ref "D8") (pin "C") (pinfunction "C_C") (pintype "passive"))
      (node (ref "LED8") (pin "A") (pinfunction "A_A") (pintype "passive"))
      (node (ref "Q13") (pin "S") (pinfunction "S_S") (pintype "bidirectional"))
      (node (ref "Q14") (pin "S") (pinfunction "S_S") (pintype "bidirectional"))
      (node (ref "R44") (pin "2") (pinfunction "2_2") (pintype "passive"))
    )
    (net (code "78") (name "S_SWITCH_1") (class "Default")
      (node (ref "C1") (pin "2") (pinfunction "2_2") (pintype "passive"))
      (node (ref "D1") (pin "C") (pinfunction "C_C") (pintype "passive"))
      (node (ref "LED1") (pin "A") (pinfunction "A_A") (pintype "passive"))
      (node (ref "Q1") (pin "S") (pinfunction "S_S") (pintype "bidirectional"))
      (node (ref "Q4") (pin "S") (pinfunction "S_S") (pintype "bidirectional"))
      (node (ref "R7") (pin "2") (pinfunction "2_2") (pintype "passive"))
    )
    (net (code "79") (name "S_SWITCH_2") (class "Default")
      (node (ref "C3") (pin "2") (pinfunction "2_2") (pintype "passive"))
      (node (ref "D3") (pin "C") (pinfunction "C_C") (pintype "passive"))
      (node (ref "LED2") (pin "A") (pinfunction "A_A") (pintype "passive"))
      (node (ref "Q3") (pin "S") (pinfunction "S_S") (pintype "bidirectional"))
      (node (ref "Q6") (pin "S") (pinfunction "S_S") (pintype "bidirectional"))
      (node (ref "R9") (pin "2") (pinfunction "2_2") (pintype "passive"))
    )
    (net (code "80") (name "S_SWITCH_3") (class "Default")
      (node (ref "C2") (pin "2") (pinfunction "2_2") (pintype "passive"))
      (node (ref "D2") (pin "C") (pinfunction "C_C") (pintype "passive"))
      (node (ref "LED3") (pin "A") (pinfunction "A_A") (pintype "passive"))
      (node (ref "Q2") (pin "S") (pinfunction "S_S") (pintype "bidirectional"))
      (node (ref "Q5") (pin "S") (pinfunction "S_S") (pintype "bidirectional"))
      (node (ref "R8") (pin "2") (pinfunction "2_2") (pintype "passive"))
    )
    (net (code "81") (name "S_SWITCH_4") (class "Default")
      (node (ref "C23") (pin "2") (pinfunction "2_2") (pintype "passive"))
      (node (ref "D7") (pin "C") (pinfunction "C_C") (pintype "passive"))
      (node (ref "LED7") (pin "A") (pinfunction "A_A") (pintype "passive"))
      (node (ref "Q11") (pin "S") (pinfunction "S_S") (pintype "bidirectional"))
      (node (ref "Q12") (pin "S") (pinfunction "S_S") (pintype "bidirectional"))
      (node (ref "R41") (pin "2") (pinfunction "2_2") (pintype "passive"))
    )
    (net (code "82") (name "TX1") (class "Default")
      (node (ref "J1") (pin "15") (pinfunction "15_15") (pintype "passive"))
    )
    (net (code "83") (name "VFB") (class "Default")
      (node (ref "R30") (pin "2") (pinfunction "2_2") (pintype "passive"))
      (node (ref "R34") (pin "1") (pinfunction "1_1") (pintype "passive"))
      (node (ref "U6") (pin "5") (pinfunction "VFB_5") (pintype "output"))
    )
    (net (code "84") (name "VIN") (class "Default")
      (node (ref "J2") (pin "15") (pinfunction "15_15") (pintype "passive"))
    )
    (net (code "85") (name "VOUT") (class "Default")
      (node (ref "C18") (pin "1") (pinfunction "1_1") (pintype "passive"))
      (node (ref "R34") (pin "2") (pinfunction "2_2") (pintype "passive"))
      (node (ref "R35") (pin "2") (pinfunction "2_2") (pintype "passive"))
    )
    (net (code "86") (name "V_SENSE_1") (class "Default")
      (node (ref "J2") (pin "4") (pinfunction "4_4") (pintype "passive"))
      (node (ref "R23") (pin "2") (pinfunction "2_2") (pintype "passive"))
      (node (ref "R26") (pin "1") (pinfunction "1_1") (pintype "passive"))
    )
    (net (code "87") (name "V_SENSE_2") (class "Default")
      (node (ref "J2") (pin "6") (pinfunction "6_6") (pintype "passive"))
      (node (ref "R24") (pin "2") (pinfunction "2_2") (pintype "passive"))
      (node (ref "R27") (pin "1") (pinfunction "1_1") (pintype "passive"))
    )
    (net (code "88") (name "V_SENSE_3") (class "Default")
      (node (ref "J2") (pin "8") (pinfunction "8_8") (pintype "passive"))
      (node (ref "R25") (pin "2") (pinfunction "2_2") (pintype "passive"))
      (node (ref "R28") (pin "1") (pinfunction "1_1") (pintype "passive"))
    )
    (net (code "89") (name "WORM_BUS+") (class "Default")
      (node (ref "D9") (pin "C") (pinfunction "C_C") (pintype "passive"))
      (node (ref "Q5") (pin "D") (pinfunction "D_D") (pintype "bidirectional"))
      (node (ref "R20") (pin "P$2") (pinfunction "2_P$2") (pintype "passive"))
      (node (ref "U7") (pin "1") (pinfunction "1_1") (pintype "passive"))
    )
    (net (code "90") (name "unconnected-(U6-PLLIN{slash}MODE-Pad1)") (class "Default")
      (node (ref "U6") (pin "1") (pinfunction "PLLIN/MODE_1") (pintype "input"))
    )
  )
)
